# Sidblaster_TicTac_-_Rev_1_1.net
KiCad netlist of a schematic drawn in EAGLE
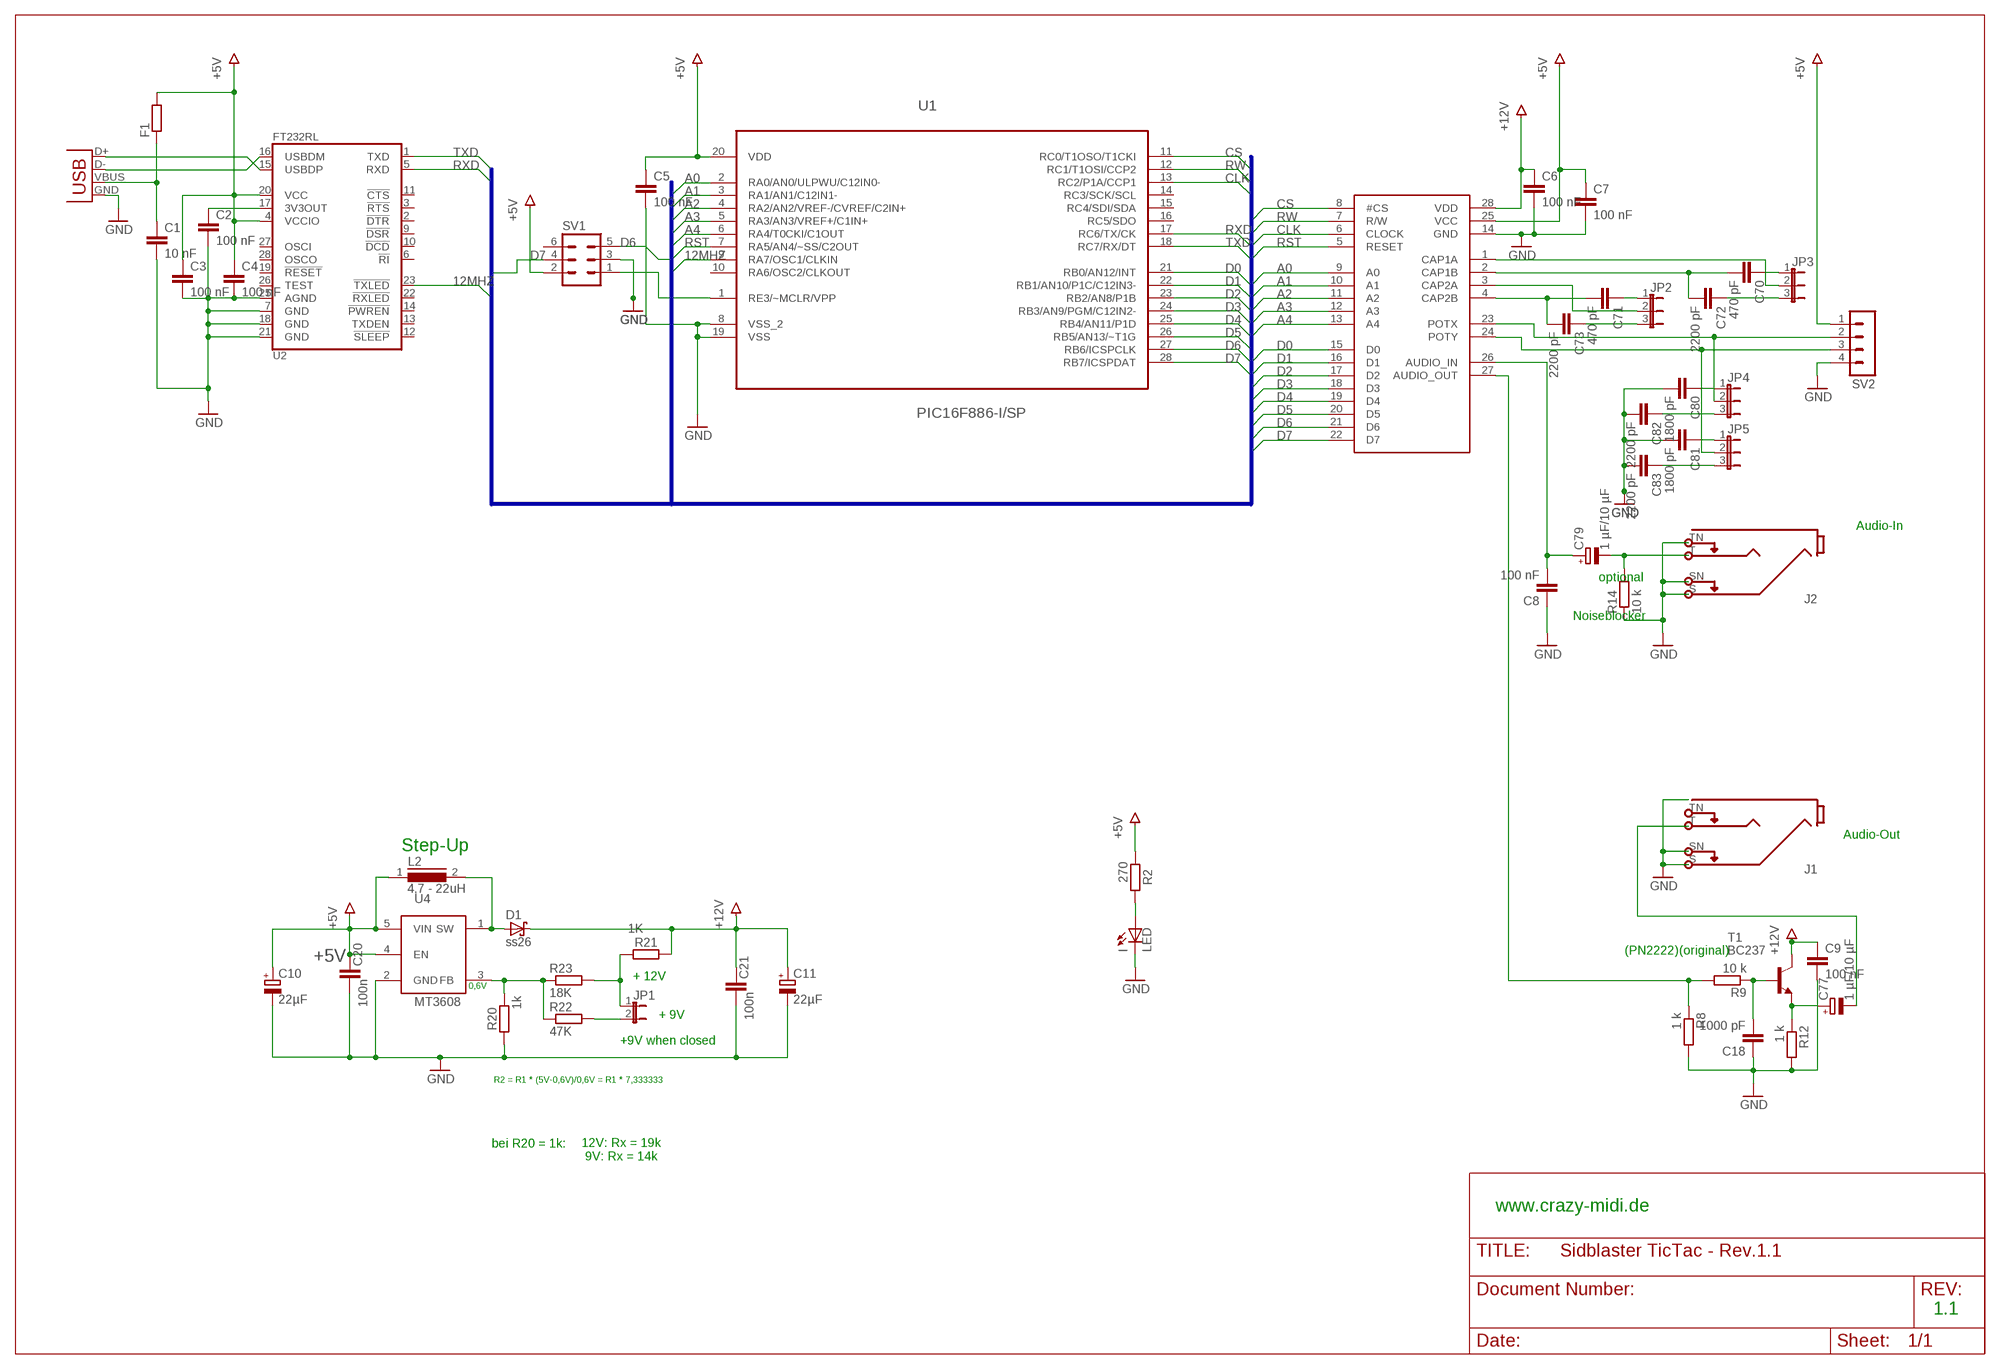
[diagram p0: schematic, sheet 1]

(export (version "E")
  (design (tool "Eeschema 10.0.6"))
  (components
    (comp (ref "C1")
      (value "10 nF")
      (footprint "eagle-import:C0805K")
      (libsource (lib "eagle-import") (part "C-EUC0805K"))
    )
    (comp (ref "C2")
      (value "100 nF")
      (footprint "eagle-import:C0805K")
      (libsource (lib "eagle-import") (part "C-EUC0805K"))
    )
    (comp (ref "C3")
      (value "100 nF")
      (footprint "eagle-import:C0805K")
      (libsource (lib "eagle-import") (part "C-EUC0805K"))
    )
    (comp (ref "C4")
      (value "100 nF")
      (footprint "eagle-import:C0805K")
      (libsource (lib "eagle-import") (part "C-EUC0805K"))
    )
    (comp (ref "C5")
      (value "100 nF")
      (footprint "eagle-import:C0805K")
      (libsource (lib "eagle-import") (part "C-EUC0805K"))
    )
    (comp (ref "C6")
      (value "100 nF")
      (footprint "eagle-import:C0805K")
      (libsource (lib "eagle-import") (part "C-EUC0805K"))
    )
    (comp (ref "C7")
      (value "100 nF")
      (footprint "eagle-import:C0805K")
      (libsource (lib "eagle-import") (part "C-EUC0805K"))
    )
    (comp (ref "C8")
      (value "100 nF")
      (footprint "eagle-import:C025-025X050")
      (libsource (lib "eagle-import") (part "C-EU025-025X050"))
    )
    (comp (ref "C9")
      (value "100 nF")
      (footprint "eagle-import:C025-025X050")
      (libsource (lib "eagle-import") (part "C-EU025-025X050"))
    )
    (comp (ref "C10")
      (value "22µF")
      (footprint "eagle-import:E2-4")
      (libsource (lib "eagle-import") (part "CPOL-EUE2-4"))
    )
    (comp (ref "C11")
      (value "22µF")
      (footprint "eagle-import:E2-4")
      (libsource (lib "eagle-import") (part "CPOL-EUE2-4"))
    )
    (comp (ref "C18")
      (value "1000 pF")
      (footprint "eagle-import:C025-025X050")
      (libsource (lib "eagle-import") (part "C-EU025-025X050"))
    )
    (comp (ref "C20")
      (value "100n")
      (footprint "eagle-import:C0805K")
      (libsource (lib "eagle-import") (part "C-EUC0805K"))
    )
    (comp (ref "C21")
      (value "100n")
      (footprint "eagle-import:C0805K")
      (libsource (lib "eagle-import") (part "C-EUC0805K"))
    )
    (comp (ref "C70")
      (value "470 pF")
      (footprint "eagle-import:C025-025X050")
      (libsource (lib "eagle-import") (part "C-EU025-025X050"))
    )
    (comp (ref "C71")
      (value "470 pF")
      (footprint "eagle-import:C025-025X050")
      (libsource (lib "eagle-import") (part "C-EU025-025X050"))
    )
    (comp (ref "C72")
      (value "2200 pF")
      (footprint "eagle-import:C025-025X050")
      (libsource (lib "eagle-import") (part "C-EU025-025X050"))
    )
    (comp (ref "C73")
      (value "2200 pF")
      (footprint "eagle-import:C025-025X050")
      (libsource (lib "eagle-import") (part "C-EU025-025X050"))
    )
    (comp (ref "C77")
      (value "1 µF/10 µF")
      (footprint "eagle-import:E5-5")
      (libsource (lib "eagle-import") (part "CPOL-EUE5-5"))
    )
    (comp (ref "C79")
      (value "1 µF/10 µF")
      (footprint "eagle-import:E5-5")
      (libsource (lib "eagle-import") (part "CPOL-EUE5-5"))
    )
    (comp (ref "C80")
      (value "1800 pF")
      (footprint "eagle-import:C025-025X050")
      (libsource (lib "eagle-import") (part "C-EU025-025X050"))
    )
    (comp (ref "C81")
      (value "1800 pF")
      (footprint "eagle-import:C025-025X050")
      (libsource (lib "eagle-import") (part "C-EU025-025X050"))
    )
    (comp (ref "C82")
      (value "2200 pF")
      (footprint "eagle-import:C025-025X050")
      (libsource (lib "eagle-import") (part "C-EU025-025X050"))
    )
    (comp (ref "C83")
      (value "2200 pF")
      (footprint "eagle-import:C025-025X050")
      (libsource (lib "eagle-import") (part "C-EU025-025X050"))
    )
    (comp (ref "D1")
      (value "ss26")
      (footprint "eagle-import:SMB")
      (libsource (lib "eagle-import") (part "SCHOTTKY-DIODESMD"))
    )
    (comp (ref "F1")
      (value "R-EU_0207/5V")
      (footprint "eagle-import:0207_5V")
      (libsource (lib "eagle-import") (part "R-EU_0207/5V"))
    )
    (comp (ref "I")
      (value "LED")
      (footprint "eagle-import:CHIPLED_1206")
      (libsource (lib "eagle-import") (part "LEDCHIPLED_1206"))
    )
    (comp (ref "J1")
      (value "MONOSW2")
      (footprint "eagle-import:NEUTRIK-NRJ4HF")
      (libsource (lib "eagle-import") (part "MONOSW2"))
    )
    (comp (ref "J2")
      (value "MONOSW2")
      (footprint "eagle-import:NEUTRIK-NRJ4HF")
      (libsource (lib "eagle-import") (part "MONOSW2"))
    )
    (comp (ref "JP1")
      (value "JP1E")
      (footprint "eagle-import:JP1")
      (libsource (lib "eagle-import") (part "JP1E"))
    )
    (comp (ref "JP2")
      (value "JP2E")
      (footprint "eagle-import:JP2")
      (libsource (lib "eagle-import") (part "JP2E"))
    )
    (comp (ref "JP3")
      (value "JP2E")
      (footprint "eagle-import:JP2")
      (libsource (lib "eagle-import") (part "JP2E"))
    )
    (comp (ref "JP4")
      (value "JP2E")
      (footprint "eagle-import:JP2")
      (libsource (lib "eagle-import") (part "JP2E"))
    )
    (comp (ref "JP5")
      (value "JP2E")
      (footprint "eagle-import:JP2")
      (libsource (lib "eagle-import") (part "JP2E"))
    )
    (comp (ref "L2")
      (value "4,7 - 22uH")
      (footprint "eagle-import:DR74")
      (libsource (lib "eagle-import") (part "DR74"))
    )
    (comp (ref "R2")
      (value "270")
      (footprint "eagle-import:M0805")
      (libsource (lib "eagle-import") (part "R-EU_M0805"))
    )
    (comp (ref "R8")
      (value "1 k")
      (footprint "eagle-import:0207_10")
      (libsource (lib "eagle-import") (part "R-EU_0207/10"))
    )
    (comp (ref "R9")
      (value "10 k")
      (footprint "eagle-import:0207_10")
      (libsource (lib "eagle-import") (part "R-EU_0207/10"))
    )
    (comp (ref "R12")
      (value "1 k")
      (footprint "eagle-import:0207_10")
      (libsource (lib "eagle-import") (part "R-EU_0207/10"))
    )
    (comp (ref "R14")
      (value "10 k")
      (footprint "eagle-import:0207_10")
      (libsource (lib "eagle-import") (part "R-EU_0207/10"))
    )
    (comp (ref "R20")
      (value "1k")
      (footprint "eagle-import:M0805")
      (libsource (lib "eagle-import") (part "R-EU_M0805"))
    )
    (comp (ref "R21")
      (value "1K")
      (footprint "eagle-import:M0805")
      (libsource (lib "eagle-import") (part "R-EU_M0805"))
    )
    (comp (ref "R22")
      (value "47K")
      (footprint "eagle-import:M0805")
      (libsource (lib "eagle-import") (part "R-EU_M0805"))
    )
    (comp (ref "R23")
      (value "18K")
      (footprint "eagle-import:M0805")
      (libsource (lib "eagle-import") (part "R-EU_M0805"))
    )
    (comp (ref "SV1")
      (value "MA03-2")
      (footprint "eagle-import:MA03-2")
      (libsource (lib "eagle-import") (part "MA03-2"))
    )
    (comp (ref "SV2")
      (value "MA04-1")
      (footprint "eagle-import:MA04-1")
      (libsource (lib "eagle-import") (part "MA04-1"))
    )
    (comp (ref "T1")
      (value "BC237")
      (footprint "eagle-import:TO92")
      (libsource (lib "eagle-import") (part "BC237"))
    )
    (comp (ref "U1")
      (value "PIC16F886-I/SP")
      (footprint "eagle-import:DIP254P762X508-28")
      (fields (field (name "MF") "Microchip"))
      (libsource (lib "eagle-import") (part "PIC16F886-I/SP"))
    )
    (comp (ref "U2")
      (value "FT232RL")
      (footprint "eagle-import:SSOP28-LD")
      (fields (field (name "MF") "FTDI"))
      (libsource (lib "eagle-import") (part "FT232RL"))
    )
    (comp (ref "U3")
      (value "6581")
      (footprint "eagle-import:DIL28-6")
      (libsource (lib "eagle-import") (part "6581"))
    )
    (comp (ref "U4")
      (value "MT3608")
      (footprint "eagle-import:SOT23-6")
      (libsource (lib "eagle-import") (part "MT3608"))
    )
    (comp (ref "X1")
      (value "USB-B-H")
      (footprint "eagle-import:USB-B-H")
      (libsource (lib "eagle-import") (part "USB-B-H"))
    )
  )
  (nets
    (net (code "1") (name "+5V") (class "Default")
      (node (ref "C10") (pin "+") (pinfunction "+_+") (pintype "passive"))
      (node (ref "C20") (pin "2") (pinfunction "2_2") (pintype "passive"))
      (node (ref "C3") (pin "1") (pinfunction "1_1") (pintype "passive"))
      (node (ref "C4") (pin "1") (pinfunction "1_1") (pintype "passive"))
      (node (ref "C5") (pin "1") (pinfunction "1_1") (pintype "passive"))
      (node (ref "C7") (pin "1") (pinfunction "1_1") (pintype "passive"))
      (node (ref "F1") (pin "2") (pinfunction "2_2") (pintype "passive"))
      (node (ref "L2") (pin "1") (pinfunction "1_1") (pintype "passive"))
      (node (ref "R2") (pin "2") (pinfunction "2_2") (pintype "passive"))
      (node (ref "SV1") (pin "2") (pinfunction "2_2") (pintype "passive"))
      (node (ref "SV2") (pin "1") (pinfunction "1_1") (pintype "passive"))
      (node (ref "U1") (pin "20") (pinfunction "VDD_20") (pintype "power_in"))
      (node (ref "U2") (pin "20") (pinfunction "VCC_20") (pintype "power_in"))
      (node (ref "U2") (pin "4") (pinfunction "VCCIO_4") (pintype "power_in"))
      (node (ref "U3") (pin "25") (pinfunction "VCC_25") (pintype "bidirectional"))
      (node (ref "U4") (pin "4") (pinfunction "EN_4") (pintype "bidirectional"))
      (node (ref "U4") (pin "5") (pinfunction "VIN_5") (pintype "bidirectional"))
    )
    (net (code "2") (name "+12V") (class "Default")
      (node (ref "C11") (pin "+") (pinfunction "+_+") (pintype "passive"))
      (node (ref "C21") (pin "2") (pinfunction "2_2") (pintype "passive"))
      (node (ref "C6") (pin "1") (pinfunction "1_1") (pintype "passive"))
      (node (ref "C9") (pin "1") (pinfunction "1_1") (pintype "passive"))
      (node (ref "D1") (pin "C") (pinfunction "C_C") (pintype "passive"))
      (node (ref "R21") (pin "1") (pinfunction "1_1") (pintype "passive"))
      (node (ref "T1") (pin "3") (pinfunction "C_3") (pintype "passive"))
      (node (ref "U3") (pin "28") (pinfunction "VDD_28") (pintype "bidirectional"))
    )
    (net (code "3") (name "/12MHZ") (class "Default")
      (node (ref "U1") (pin "9") (pinfunction "RA7/OSC1/CLKIN_9") (pintype "bidirectional"))
      (node (ref "U2") (pin "23") (pinfunction "~{TXLED}_23") (pintype "input"))
    )
    (net (code "4") (name "/A0") (class "Default")
      (node (ref "U1") (pin "2") (pinfunction "RA0/AN0/ULPWU/C12IN0-_2") (pintype "bidirectional"))
      (node (ref "U3") (pin "9") (pinfunction "A0_9") (pintype "bidirectional"))
    )
    (net (code "5") (name "/A1") (class "Default")
      (node (ref "U1") (pin "3") (pinfunction "RA1/AN1/C12IN1-_3") (pintype "bidirectional"))
      (node (ref "U3") (pin "10") (pinfunction "A1_10") (pintype "bidirectional"))
    )
    (net (code "6") (name "/A2") (class "Default")
      (node (ref "U1") (pin "4") (pinfunction "RA2/AN2/VREF-/CVREF/C2IN+_4") (pintype "bidirectional"))
      (node (ref "U3") (pin "11") (pinfunction "A2_11") (pintype "bidirectional"))
    )
    (net (code "7") (name "/A3") (class "Default")
      (node (ref "U1") (pin "5") (pinfunction "RA3/AN3/VREF+/C1IN+_5") (pintype "bidirectional"))
      (node (ref "U3") (pin "12") (pinfunction "A3_12") (pintype "bidirectional"))
    )
    (net (code "8") (name "/A4") (class "Default")
      (node (ref "U1") (pin "6") (pinfunction "RA4/T0CKI/C1OUT_6") (pintype "bidirectional"))
      (node (ref "U3") (pin "13") (pinfunction "A4_13") (pintype "bidirectional"))
    )
    (net (code "9") (name "/CLK") (class "Default")
      (node (ref "U1") (pin "13") (pinfunction "RC2/P1A/CCP1_13") (pintype "bidirectional"))
      (node (ref "U3") (pin "6") (pinfunction "CLOCK_6") (pintype "bidirectional"))
    )
    (net (code "10") (name "/CS") (class "Default")
      (node (ref "U1") (pin "11") (pinfunction "RC0/T1OSO/T1CKI_11") (pintype "bidirectional"))
      (node (ref "U3") (pin "8") (pinfunction "#CS_8") (pintype "bidirectional"))
    )
    (net (code "11") (name "/D0") (class "Default")
      (node (ref "U1") (pin "21") (pinfunction "RB0/AN12/INT_21") (pintype "bidirectional"))
      (node (ref "U3") (pin "15") (pinfunction "D0_15") (pintype "bidirectional"))
    )
    (net (code "12") (name "/D1") (class "Default")
      (node (ref "U1") (pin "22") (pinfunction "RB1/AN10/P1C/C12IN3-_22") (pintype "bidirectional"))
      (node (ref "U3") (pin "16") (pinfunction "D1_16") (pintype "bidirectional"))
    )
    (net (code "13") (name "/D2") (class "Default")
      (node (ref "U1") (pin "23") (pinfunction "RB2/AN8/P1B_23") (pintype "bidirectional"))
      (node (ref "U3") (pin "17") (pinfunction "D2_17") (pintype "bidirectional"))
    )
    (net (code "14") (name "/D3") (class "Default")
      (node (ref "U1") (pin "24") (pinfunction "RB3/AN9/PGM/C12IN2-_24") (pintype "bidirectional"))
      (node (ref "U3") (pin "18") (pinfunction "D3_18") (pintype "bidirectional"))
    )
    (net (code "15") (name "/D4") (class "Default")
      (node (ref "U1") (pin "25") (pinfunction "RB4/AN11/P1D_25") (pintype "bidirectional"))
      (node (ref "U3") (pin "19") (pinfunction "D4_19") (pintype "bidirectional"))
    )
    (net (code "16") (name "/D5") (class "Default")
      (node (ref "U1") (pin "26") (pinfunction "RB5/AN13/~{T1G}_26") (pintype "bidirectional"))
      (node (ref "U3") (pin "20") (pinfunction "D5_20") (pintype "bidirectional"))
    )
    (net (code "17") (name "/D6") (class "Default")
      (node (ref "SV1") (pin "5") (pinfunction "5_5") (pintype "passive"))
      (node (ref "U1") (pin "27") (pinfunction "RB6/ICSPCLK_27") (pintype "bidirectional"))
      (node (ref "U3") (pin "21") (pinfunction "D6_21") (pintype "bidirectional"))
    )
    (net (code "18") (name "/D7") (class "Default")
      (node (ref "SV1") (pin "4") (pinfunction "4_4") (pintype "passive"))
      (node (ref "U1") (pin "28") (pinfunction "RB7/ICSPDAT_28") (pintype "bidirectional"))
      (node (ref "U3") (pin "22") (pinfunction "D7_22") (pintype "bidirectional"))
    )
    (net (code "19") (name "/RST") (class "Default")
      (node (ref "U1") (pin "7") (pinfunction "RA5/AN4/~{SS/C2OUT}_7") (pintype "bidirectional"))
      (node (ref "U3") (pin "5") (pinfunction "RESET_5") (pintype "bidirectional"))
    )
    (net (code "20") (name "/RW") (class "Default")
      (node (ref "U1") (pin "12") (pinfunction "RC1/T1OSI/CCP2_12") (pintype "bidirectional"))
      (node (ref "U3") (pin "7") (pinfunction "R/W_7") (pintype "bidirectional"))
    )
    (net (code "21") (name "/RXD") (class "Default")
      (node (ref "U1") (pin "17") (pinfunction "RC6/TX/CK_17") (pintype "bidirectional"))
      (node (ref "U2") (pin "5") (pinfunction "RXD_5") (pintype "input"))
    )
    (net (code "22") (name "/TXD") (class "Default")
      (node (ref "U1") (pin "18") (pinfunction "RC7/RX/DT_18") (pintype "bidirectional"))
      (node (ref "U2") (pin "1") (pinfunction "TXD_1") (pintype "output"))
    )
    (net (code "23") (name "GND") (class "Default")
      (node (ref "C1") (pin "2") (pinfunction "2_2") (pintype "passive"))
      (node (ref "C10") (pin "-") (pinfunction "-_-") (pintype "passive"))
      (node (ref "C11") (pin "-") (pinfunction "-_-") (pintype "passive"))
      (node (ref "C18") (pin "1") (pinfunction "1_1") (pintype "passive"))
      (node (ref "C2") (pin "2") (pinfunction "2_2") (pintype "passive"))
      (node (ref "C20") (pin "1") (pinfunction "1_1") (pintype "passive"))
      (node (ref "C21") (pin "1") (pinfunction "1_1") (pintype "passive"))
      (node (ref "C3") (pin "2") (pinfunction "2_2") (pintype "passive"))
      (node (ref "C4") (pin "2") (pinfunction "2_2") (pintype "passive"))
      (node (ref "C5") (pin "2") (pinfunction "2_2") (pintype "passive"))
      (node (ref "C6") (pin "2") (pinfunction "2_2") (pintype "passive"))
      (node (ref "C7") (pin "2") (pinfunction "2_2") (pintype "passive"))
      (node (ref "C8") (pin "1") (pinfunction "1_1") (pintype "passive"))
      (node (ref "C80") (pin "2") (pinfunction "2_2") (pintype "passive"))
      (node (ref "C81") (pin "2") (pinfunction "2_2") (pintype "passive"))
      (node (ref "C82") (pin "2") (pinfunction "2_2") (pintype "passive"))
      (node (ref "C83") (pin "2") (pinfunction "2_2") (pintype "passive"))
      (node (ref "C9") (pin "2") (pinfunction "2_2") (pintype "passive"))
      (node (ref "I") (pin "C") (pinfunction "C_C") (pintype "passive"))
      (node (ref "J1") (pin "S") (pinfunction "S_S") (pintype "passive"))
      (node (ref "J1") (pin "SN") (pinfunction "SN_SN") (pintype "passive"))
      (node (ref "J2") (pin "S") (pinfunction "S_S") (pintype "passive"))
      (node (ref "J2") (pin "SN") (pinfunction "SN_SN") (pintype "passive"))
      (node (ref "J2") (pin "TN") (pinfunction "TN_TN") (pintype "passive"))
      (node (ref "R12") (pin "2") (pinfunction "2_2") (pintype "passive"))
      (node (ref "R14") (pin "1") (pinfunction "1_1") (pintype "passive"))
      (node (ref "R20") (pin "2") (pinfunction "2_2") (pintype "passive"))
      (node (ref "R8") (pin "2") (pinfunction "2_2") (pintype "passive"))
      (node (ref "SV1") (pin "3") (pinfunction "3_3") (pintype "passive"))
      (node (ref "SV2") (pin "4") (pinfunction "4_4") (pintype "passive"))
      (node (ref "U1") (pin "19") (pinfunction "VSS_19") (pintype "passive"))
      (node (ref "U1") (pin "8") (pinfunction "VSS_2_8") (pintype "passive"))
      (node (ref "U2") (pin "18") (pinfunction "GND_18") (pintype "power_in"))
      (node (ref "U2") (pin "21") (pinfunction "GND_21") (pintype "power_in"))
      (node (ref "U2") (pin "25") (pinfunction "AGND_25") (pintype "power_in"))
      (node (ref "U2") (pin "7") (pinfunction "GND_7") (pintype "power_in"))
      (node (ref "U3") (pin "14") (pinfunction "GND_14") (pintype "bidirectional"))
      (node (ref "U4") (pin "2") (pinfunction "GND_2") (pintype "bidirectional"))
      (node (ref "X1") (pin "GND") (pinfunction "GND_GND") (pintype "bidirectional"))
    )
    (net (code "24") (name "Net-(C1-Pad1)") (class "Default")
      (node (ref "C1") (pin "1") (pinfunction "1_1") (pintype "passive"))
      (node (ref "F1") (pin "1") (pinfunction "1_1") (pintype "passive"))
      (node (ref "X1") (pin "VBUS") (pinfunction "VBUS_VBUS") (pintype "bidirectional"))
    )
    (net (code "25") (name "Net-(C70-Pad1)") (class "Default")
      (node (ref "C70") (pin "1") (pinfunction "1_1") (pintype "passive"))
      (node (ref "JP3") (pin "1") (pinfunction "1_1") (pintype "passive"))
    )
    (net (code "26") (name "Net-(C71-Pad1)") (class "Default")
      (node (ref "C71") (pin "1") (pinfunction "1_1") (pintype "passive"))
      (node (ref "JP2") (pin "1") (pinfunction "1_1") (pintype "passive"))
    )
    (net (code "27") (name "Net-(C72-Pad1)") (class "Default")
      (node (ref "C72") (pin "1") (pinfunction "1_1") (pintype "passive"))
      (node (ref "JP3") (pin "3") (pinfunction "3_3") (pintype "passive"))
    )
    (net (code "28") (name "Net-(C73-Pad1)") (class "Default")
      (node (ref "C73") (pin "1") (pinfunction "1_1") (pintype "passive"))
      (node (ref "JP2") (pin "3") (pinfunction "3_3") (pintype "passive"))
    )
    (net (code "29") (name "Net-(C77-Pad-)") (class "Default")
      (node (ref "C77") (pin "-") (pinfunction "-_-") (pintype "passive"))
      (node (ref "J1") (pin "T") (pinfunction "T_T") (pintype "passive"))
    )
    (net (code "30") (name "Net-(C79-Pad-)") (class "Default")
      (node (ref "C79") (pin "-") (pinfunction "-_-") (pintype "passive"))
      (node (ref "J2") (pin "T") (pinfunction "T_T") (pintype "passive"))
      (node (ref "R14") (pin "2") (pinfunction "2_2") (pintype "passive"))
    )
    (net (code "31") (name "Net-(C80-Pad1)") (class "Default")
      (node (ref "C80") (pin "1") (pinfunction "1_1") (pintype "passive"))
      (node (ref "JP4") (pin "1") (pinfunction "1_1") (pintype "passive"))
    )
    (net (code "32") (name "Net-(C81-Pad1)") (class "Default")
      (node (ref "C81") (pin "1") (pinfunction "1_1") (pintype "passive"))
      (node (ref "JP5") (pin "1") (pinfunction "1_1") (pintype "passive"))
    )
    (net (code "33") (name "Net-(C82-Pad1)") (class "Default")
      (node (ref "C82") (pin "1") (pinfunction "1_1") (pintype "passive"))
      (node (ref "JP4") (pin "3") (pinfunction "3_3") (pintype "passive"))
    )
    (net (code "34") (name "Net-(C83-Pad1)") (class "Default")
      (node (ref "C83") (pin "1") (pinfunction "1_1") (pintype "passive"))
      (node (ref "JP5") (pin "3") (pinfunction "3_3") (pintype "passive"))
    )
    (net (code "35") (name "Net-(I-PadA)") (class "Default")
      (node (ref "I") (pin "A") (pinfunction "A_A") (pintype "passive"))
      (node (ref "R2") (pin "1") (pinfunction "1_1") (pintype "passive"))
    )
    (net (code "36") (name "Net-(JP1-Pad1)") (class "Default")
      (node (ref "JP1") (pin "1") (pinfunction "1_1") (pintype "passive"))
      (node (ref "R21") (pin "2") (pinfunction "2_2") (pintype "passive"))
      (node (ref "R23") (pin "2") (pinfunction "2_2") (pintype "passive"))
    )
    (net (code "37") (name "Net-(JP1-Pad2)") (class "Default")
      (node (ref "JP1") (pin "2") (pinfunction "2_2") (pintype "passive"))
      (node (ref "R22") (pin "2") (pinfunction "2_2") (pintype "passive"))
    )
    (net (code "38") (name "Net-(T1-B)") (class "Default")
      (node (ref "C18") (pin "2") (pinfunction "2_2") (pintype "passive"))
      (node (ref "R9") (pin "1") (pinfunction "1_1") (pintype "passive"))
      (node (ref "T1") (pin "2") (pinfunction "B_2") (pintype "passive"))
    )
    (net (code "39") (name "Net-(T1-E)") (class "Default")
      (node (ref "C77") (pin "+") (pinfunction "+_+") (pintype "passive"))
      (node (ref "R12") (pin "1") (pinfunction "1_1") (pintype "passive"))
      (node (ref "T1") (pin "1") (pinfunction "E_1") (pintype "passive"))
    )
    (net (code "40") (name "Net-(U1-RE3{slash}~{MCLR{slash}VPP})") (class "Default")
      (node (ref "SV1") (pin "1") (pinfunction "1_1") (pintype "passive"))
      (node (ref "U1") (pin "1") (pinfunction "RE3/~{MCLR/VPP}_1") (pintype "input"))
    )
    (net (code "41") (name "Net-(U2-3V3OUT)") (class "Default")
      (node (ref "C2") (pin "1") (pinfunction "1_1") (pintype "passive"))
      (node (ref "U2") (pin "17") (pinfunction "3V3OUT_17") (pintype "power_in"))
    )
    (net (code "42") (name "Net-(U2-USBDM)") (class "Default")
      (node (ref "U2") (pin "16") (pinfunction "USBDM_16") (pintype "bidirectional"))
      (node (ref "X1") (pin "D-") (pinfunction "D-_D-") (pintype "bidirectional"))
    )
    (net (code "43") (name "Net-(U2-USBDP)") (class "Default")
      (node (ref "U2") (pin "15") (pinfunction "USBDP_15") (pintype "bidirectional"))
      (node (ref "X1") (pin "D+") (pinfunction "D+_D+") (pintype "bidirectional"))
    )
    (net (code "44") (name "Net-(U3-AUDIO_IN)") (class "Default")
      (node (ref "C79") (pin "+") (pinfunction "+_+") (pintype "passive"))
      (node (ref "C8") (pin "2") (pinfunction "2_2") (pintype "passive"))
      (node (ref "U3") (pin "26") (pinfunction "AUDIO_IN_26") (pintype "bidirectional"))
    )
    (net (code "45") (name "Net-(U3-AUDIO_OUT)") (class "Default")
      (node (ref "R8") (pin "1") (pinfunction "1_1") (pintype "passive"))
      (node (ref "R9") (pin "2") (pinfunction "2_2") (pintype "passive"))
      (node (ref "U3") (pin "27") (pinfunction "AUDIO_OUT_27") (pintype "bidirectional"))
    )
    (net (code "46") (name "Net-(U3-CAP1A)") (class "Default")
      (node (ref "JP3") (pin "2") (pinfunction "2_2") (pintype "passive"))
      (node (ref "U3") (pin "1") (pinfunction "CAP1A_1") (pintype "bidirectional"))
    )
    (net (code "47") (name "Net-(U3-CAP1B)") (class "Default")
      (node (ref "C70") (pin "2") (pinfunction "2_2") (pintype "passive"))
      (node (ref "C72") (pin "2") (pinfunction "2_2") (pintype "passive"))
      (node (ref "U3") (pin "2") (pinfunction "CAP1B_2") (pintype "bidirectional"))
    )
    (net (code "48") (name "Net-(U3-CAP2A)") (class "Default")
      (node (ref "JP2") (pin "2") (pinfunction "2_2") (pintype "passive"))
      (node (ref "U3") (pin "3") (pinfunction "CAP2A_3") (pintype "bidirectional"))
    )
    (net (code "49") (name "Net-(U3-CAP2B)") (class "Default")
      (node (ref "C71") (pin "2") (pinfunction "2_2") (pintype "passive"))
      (node (ref "C73") (pin "2") (pinfunction "2_2") (pintype "passive"))
      (node (ref "U3") (pin "4") (pinfunction "CAP2B_4") (pintype "bidirectional"))
    )
    (net (code "50") (name "Net-(U3-POTX)") (class "Default")
      (node (ref "JP4") (pin "2") (pinfunction "2_2") (pintype "passive"))
      (node (ref "SV2") (pin "2") (pinfunction "2_2") (pintype "passive"))
      (node (ref "U3") (pin "23") (pinfunction "POTX_23") (pintype "bidirectional"))
    )
    (net (code "51") (name "Net-(U3-POTY)") (class "Default")
      (node (ref "JP5") (pin "2") (pinfunction "2_2") (pintype "passive"))
      (node (ref "SV2") (pin "3") (pinfunction "3_3") (pintype "passive"))
      (node (ref "U3") (pin "24") (pinfunction "POTY_24") (pintype "bidirectional"))
    )
    (net (code "52") (name "Net-(U4-FB)") (class "Default")
      (node (ref "R20") (pin "1") (pinfunction "1_1") (pintype "passive"))
      (node (ref "R22") (pin "1") (pinfunction "1_1") (pintype "passive"))
      (node (ref "R23") (pin "1") (pinfunction "1_1") (pintype "passive"))
      (node (ref "U4") (pin "3") (pinfunction "FB_3") (pintype "bidirectional"))
    )
    (net (code "53") (name "Net-(U4-SW)") (class "Default")
      (node (ref "D1") (pin "A") (pinfunction "A_A") (pintype "passive"))
      (node (ref "L2") (pin "2") (pinfunction "2_2") (pintype "passive"))
      (node (ref "U4") (pin "1") (pinfunction "SW_1") (pintype "bidirectional"))
    )
    (net (code "54") (name "unconnected-(J1-PadTN)") (class "Default")
      (node (ref "J1") (pin "TN") (pinfunction "TN_TN") (pintype "passive"))
    )
    (net (code "55") (name "unconnected-(SV1-Pad6)") (class "Default")
      (node (ref "SV1") (pin "6") (pinfunction "6_6") (pintype "passive"))
    )
    (net (code "56") (name "unconnected-(U1-RA6{slash}OSC2{slash}CLKOUT-Pad10)") (class "Default")
      (node (ref "U1") (pin "10") (pinfunction "RA6/OSC2/CLKOUT_10") (pintype "bidirectional"))
    )
    (net (code "57") (name "unconnected-(U1-RC3{slash}SCK{slash}SCL-Pad14)") (class "Default")
      (node (ref "U1") (pin "14") (pinfunction "RC3/SCK/SCL_14") (pintype "bidirectional"))
    )
    (net (code "58") (name "unconnected-(U1-RC4{slash}SDI{slash}SDA-Pad15)") (class "Default")
      (node (ref "U1") (pin "15") (pinfunction "RC4/SDI/SDA_15") (pintype "bidirectional"))
    )
    (net (code "59") (name "unconnected-(U1-RC5{slash}SDO-Pad16)") (class "Default")
      (node (ref "U1") (pin "16") (pinfunction "RC5/SDO_16") (pintype "bidirectional"))
    )
    (net (code "60") (name "unconnected-(U2-OSCI-Pad27)") (class "Default")
      (node (ref "U2") (pin "27") (pinfunction "OSCI_27") (pintype "no_connect"))
    )
    (net (code "61") (name "unconnected-(U2-OSCO-Pad28)") (class "Default")
      (node (ref "U2") (pin "28") (pinfunction "OSCO_28") (pintype "output"))
    )
    (net (code "62") (name "unconnected-(U2-TEST-Pad26)") (class "Default")
      (node (ref "U2") (pin "26") (pinfunction "TEST_26") (pintype "input"))
    )
    (net (code "63") (name "unconnected-(U2-TXDEN-Pad13)") (class "Default")
      (node (ref "U2") (pin "13") (pinfunction "TXDEN_13") (pintype "no_connect"))
    )
    (net (code "64") (name "unconnected-(U2-~{CTS}-Pad11)") (class "Default")
      (node (ref "U2") (pin "11") (pinfunction "~{CTS}_11") (pintype "input"))
    )
    (net (code "65") (name "unconnected-(U2-~{DCD}-Pad10)") (class "Default")
      (node (ref "U2") (pin "10") (pinfunction "~{DCD}_10") (pintype "no_connect"))
    )
    (net (code "66") (name "unconnected-(U2-~{DSR}-Pad9)") (class "Default")
      (node (ref "U2") (pin "9") (pinfunction "~{DSR}_9") (pintype "no_connect"))
    )
    (net (code "67") (name "unconnected-(U2-~{DTR}-Pad2)") (class "Default")
      (node (ref "U2") (pin "2") (pinfunction "~{DTR}_2") (pintype "output"))
    )
    (net (code "68") (name "unconnected-(U2-~{PWREN}-Pad14)") (class "Default")
      (node (ref "U2") (pin "14") (pinfunction "~{PWREN}_14") (pintype "no_connect"))
    )
    (net (code "69") (name "unconnected-(U2-~{RESET}-Pad19)") (class "Default")
      (node (ref "U2") (pin "19") (pinfunction "~{RESET}_19") (pintype "no_connect"))
    )
    (net (code "70") (name "unconnected-(U2-~{RI}-Pad6)") (class "Default")
      (node (ref "U2") (pin "6") (pinfunction "~{RI}_6") (pintype "no_connect"))
    )
    (net (code "71") (name "unconnected-(U2-~{RTS}-Pad3)") (class "Default")
      (node (ref "U2") (pin "3") (pinfunction "~{RTS}_3") (pintype "output"))
    )
    (net (code "72") (name "unconnected-(U2-~{RXLED}-Pad22)") (class "Default")
      (node (ref "U2") (pin "22") (pinfunction "~{RXLED}_22") (pintype "input"))
    )
    (net (code "73") (name "unconnected-(U2-~{SLEEP}-Pad12)") (class "Default")
      (node (ref "U2") (pin "12") (pinfunction "~{SLEEP}_12") (pintype "no_connect"))
    )
  )
)
